# PGTNX05_mainboard.net
KiCad netlist of a schematic drawn in EAGLE
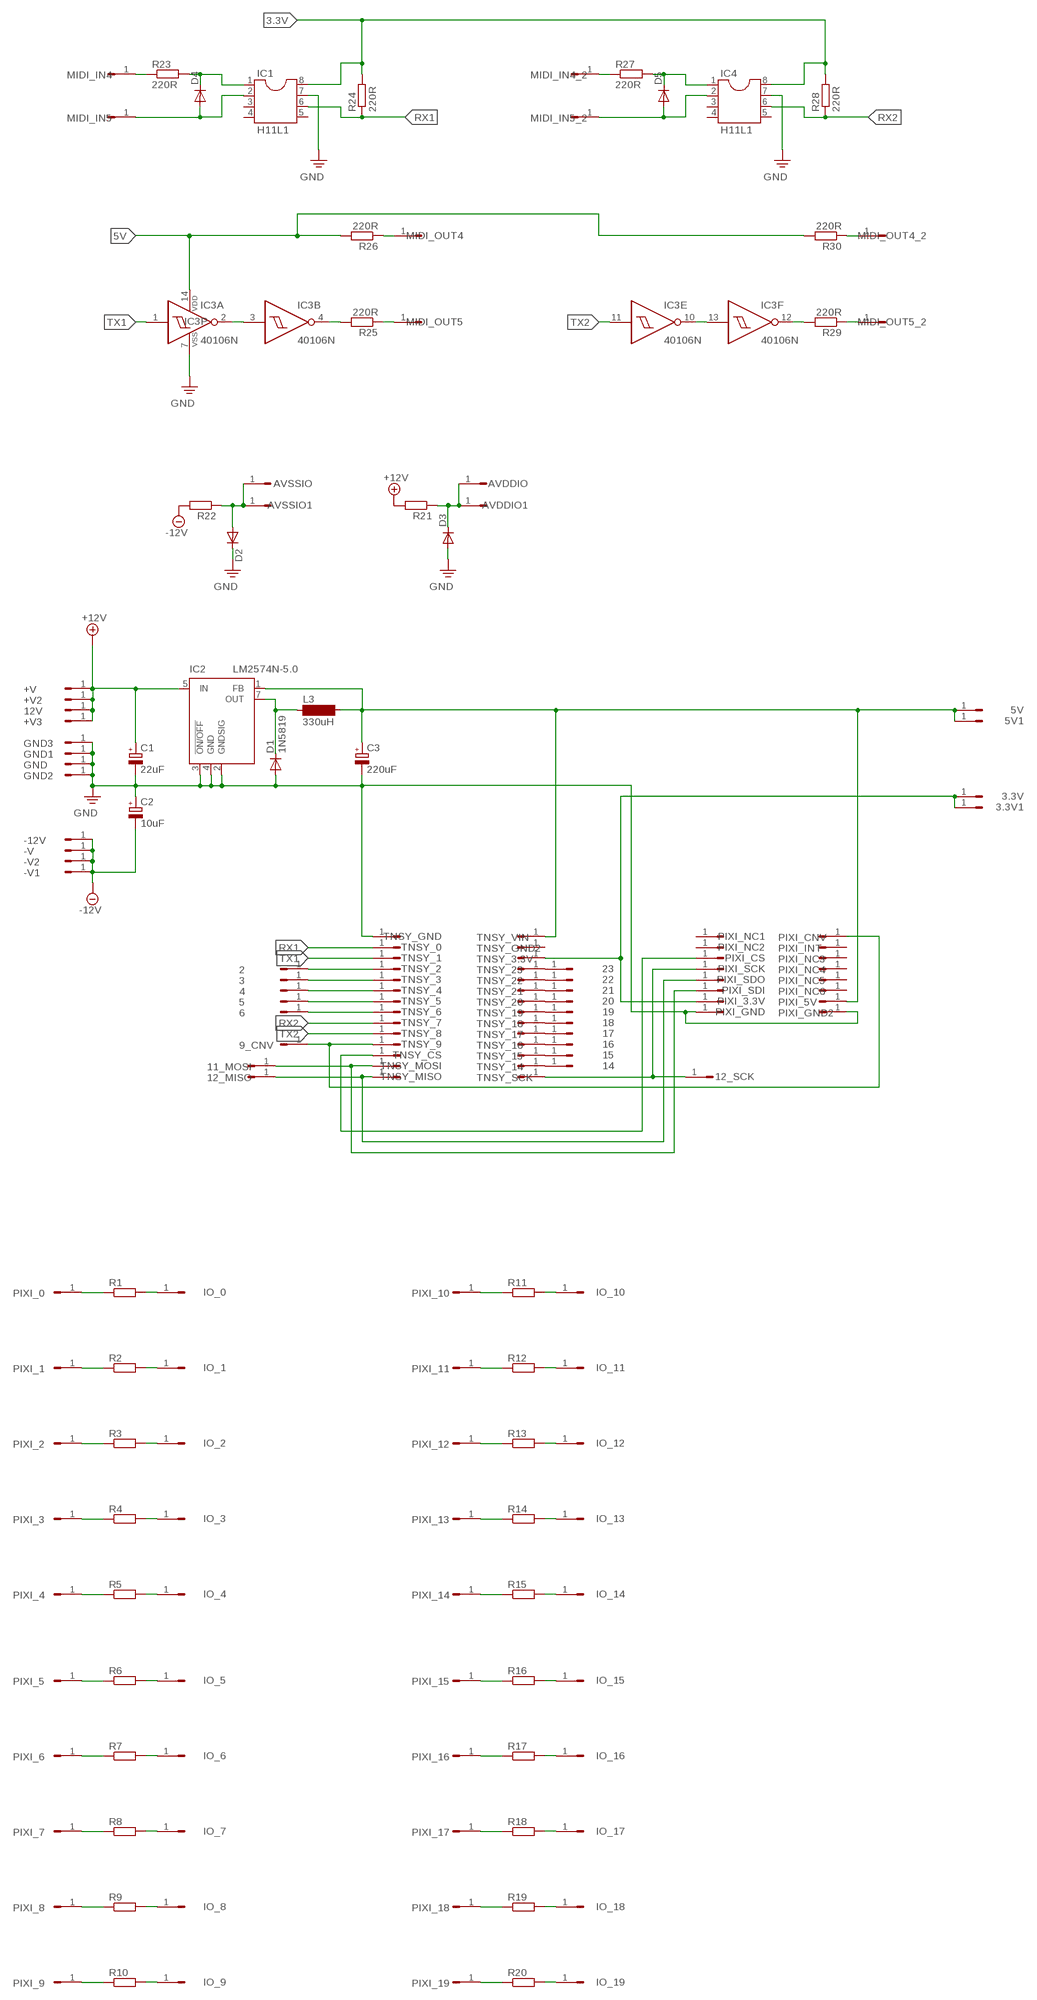
[diagram p0: schematic, sheet 1]

(export (version "E")
  (design (tool "Eeschema 10.0.6"))
  (components
    (comp (ref "+V")
      (value "HEADER/MALE/01")
      (footprint "eagle-import:HEADER_MALE_01")
      (fields (field (name "SPICEPREFIX") "X"))
      (libsource (lib "eagle-import") (part "HEADER/MALE/01"))
    )
    (comp (ref "+V2")
      (value "HEADER/MALE/01")
      (footprint "eagle-import:HEADER_MALE_01")
      (fields (field (name "SPICEPREFIX") "X"))
      (libsource (lib "eagle-import") (part "HEADER/MALE/01"))
    )
    (comp (ref "+V3")
      (value "HEADER/MALE/01")
      (footprint "eagle-import:HEADER_MALE_01")
      (fields (field (name "SPICEPREFIX") "X"))
      (libsource (lib "eagle-import") (part "HEADER/MALE/01"))
    )
    (comp (ref "-12V")
      (value "HEADER/MALE/01")
      (footprint "eagle-import:HEADER_MALE_01")
      (fields (field (name "SPICEPREFIX") "X"))
      (libsource (lib "eagle-import") (part "HEADER/MALE/01"))
    )
    (comp (ref "-V")
      (value "HEADER/MALE/01")
      (footprint "eagle-import:HEADER_MALE_01")
      (fields (field (name "SPICEPREFIX") "X"))
      (libsource (lib "eagle-import") (part "HEADER/MALE/01"))
    )
    (comp (ref "-V1")
      (value "HEADER/MALE/01")
      (footprint "eagle-import:HEADER_MALE_01")
      (fields (field (name "SPICEPREFIX") "X"))
      (libsource (lib "eagle-import") (part "HEADER/MALE/01"))
    )
    (comp (ref "-V2")
      (value "HEADER/MALE/01")
      (footprint "eagle-import:HEADER_MALE_01")
      (fields (field (name "SPICEPREFIX") "X"))
      (libsource (lib "eagle-import") (part "HEADER/MALE/01"))
    )
    (comp (ref "2")
      (value "HEADER/MALE/01")
      (footprint "eagle-import:HEADER_MALE_01")
      (fields (field (name "SPICEPREFIX") "X"))
      (libsource (lib "eagle-import") (part "HEADER/MALE/01"))
    )
    (comp (ref "3")
      (value "HEADER/MALE/01")
      (footprint "eagle-import:HEADER_MALE_01")
      (fields (field (name "SPICEPREFIX") "X"))
      (libsource (lib "eagle-import") (part "HEADER/MALE/01"))
    )
    (comp (ref "3.3V")
      (value "HEADER/MALE/01")
      (footprint "eagle-import:HEADER_MALE_01")
      (fields (field (name "SPICEPREFIX") "X"))
      (libsource (lib "eagle-import") (part "HEADER/MALE/01"))
    )
    (comp (ref "3.3V1")
      (value "HEADER/MALE/01")
      (footprint "eagle-import:HEADER_MALE_01")
      (fields (field (name "SPICEPREFIX") "X"))
      (libsource (lib "eagle-import") (part "HEADER/MALE/01"))
    )
    (comp (ref "4")
      (value "HEADER/MALE/01")
      (footprint "eagle-import:HEADER_MALE_01")
      (fields (field (name "SPICEPREFIX") "X"))
      (libsource (lib "eagle-import") (part "HEADER/MALE/01"))
    )
    (comp (ref "5")
      (value "HEADER/MALE/01")
      (footprint "eagle-import:HEADER_MALE_01")
      (fields (field (name "SPICEPREFIX") "X"))
      (libsource (lib "eagle-import") (part "HEADER/MALE/01"))
    )
    (comp (ref "5V")
      (value "HEADER/MALE/01")
      (footprint "eagle-import:HEADER_MALE_01")
      (fields (field (name "SPICEPREFIX") "X"))
      (libsource (lib "eagle-import") (part "HEADER/MALE/01"))
    )
    (comp (ref "5V1")
      (value "HEADER/MALE/01")
      (footprint "eagle-import:HEADER_MALE_01")
      (fields (field (name "SPICEPREFIX") "X"))
      (libsource (lib "eagle-import") (part "HEADER/MALE/01"))
    )
    (comp (ref "6")
      (value "HEADER/MALE/01")
      (footprint "eagle-import:HEADER_MALE_01")
      (fields (field (name "SPICEPREFIX") "X"))
      (libsource (lib "eagle-import") (part "HEADER/MALE/01"))
    )
    (comp (ref "9_CNV")
      (value "HEADER/MALE/01")
      (footprint "eagle-import:HEADER_MALE_01")
      (fields (field (name "SPICEPREFIX") "X"))
      (libsource (lib "eagle-import") (part "HEADER/MALE/01"))
    )
    (comp (ref "11_MOSI")
      (value "HEADER/MALE/01")
      (footprint "eagle-import:HEADER_MALE_01")
      (fields (field (name "SPICEPREFIX") "X"))
      (libsource (lib "eagle-import") (part "HEADER/MALE/01"))
    )
    (comp (ref "12V")
      (value "HEADER/MALE/01")
      (footprint "eagle-import:HEADER_MALE_01")
      (fields (field (name "SPICEPREFIX") "X"))
      (libsource (lib "eagle-import") (part "HEADER/MALE/01"))
    )
    (comp (ref "12_MISO")
      (value "HEADER/MALE/01")
      (footprint "eagle-import:HEADER_MALE_01")
      (fields (field (name "SPICEPREFIX") "X"))
      (libsource (lib "eagle-import") (part "HEADER/MALE/01"))
    )
    (comp (ref "12_SCK")
      (value "HEADER/MALE/01")
      (footprint "eagle-import:HEADER_MALE_01")
      (fields (field (name "SPICEPREFIX") "X"))
      (libsource (lib "eagle-import") (part "HEADER/MALE/01"))
    )
    (comp (ref "14")
      (value "HEADER/MALE/01")
      (footprint "eagle-import:HEADER_MALE_01")
      (fields (field (name "SPICEPREFIX") "X"))
      (libsource (lib "eagle-import") (part "HEADER/MALE/01"))
    )
    (comp (ref "15")
      (value "HEADER/MALE/01")
      (footprint "eagle-import:HEADER_MALE_01")
      (fields (field (name "SPICEPREFIX") "X"))
      (libsource (lib "eagle-import") (part "HEADER/MALE/01"))
    )
    (comp (ref "16")
      (value "HEADER/MALE/01")
      (footprint "eagle-import:HEADER_MALE_01")
      (fields (field (name "SPICEPREFIX") "X"))
      (libsource (lib "eagle-import") (part "HEADER/MALE/01"))
    )
    (comp (ref "17")
      (value "HEADER/MALE/01")
      (footprint "eagle-import:HEADER_MALE_01")
      (fields (field (name "SPICEPREFIX") "X"))
      (libsource (lib "eagle-import") (part "HEADER/MALE/01"))
    )
    (comp (ref "18")
      (value "HEADER/MALE/01")
      (footprint "eagle-import:HEADER_MALE_01")
      (fields (field (name "SPICEPREFIX") "X"))
      (libsource (lib "eagle-import") (part "HEADER/MALE/01"))
    )
    (comp (ref "19")
      (value "HEADER/MALE/01")
      (footprint "eagle-import:HEADER_MALE_01")
      (fields (field (name "SPICEPREFIX") "X"))
      (libsource (lib "eagle-import") (part "HEADER/MALE/01"))
    )
    (comp (ref "20")
      (value "HEADER/MALE/01")
      (footprint "eagle-import:HEADER_MALE_01")
      (fields (field (name "SPICEPREFIX") "X"))
      (libsource (lib "eagle-import") (part "HEADER/MALE/01"))
    )
    (comp (ref "21")
      (value "HEADER/MALE/01")
      (footprint "eagle-import:HEADER_MALE_01")
      (fields (field (name "SPICEPREFIX") "X"))
      (libsource (lib "eagle-import") (part "HEADER/MALE/01"))
    )
    (comp (ref "22")
      (value "HEADER/MALE/01")
      (footprint "eagle-import:HEADER_MALE_01")
      (fields (field (name "SPICEPREFIX") "X"))
      (libsource (lib "eagle-import") (part "HEADER/MALE/01"))
    )
    (comp (ref "23")
      (value "HEADER/MALE/01")
      (footprint "eagle-import:HEADER_MALE_01")
      (fields (field (name "SPICEPREFIX") "X"))
      (libsource (lib "eagle-import") (part "HEADER/MALE/01"))
    )
    (comp (ref "AVDDIO")
      (value "HEADER/MALE/01")
      (footprint "eagle-import:HEADER_MALE_01")
      (fields (field (name "SPICEPREFIX") "X"))
      (libsource (lib "eagle-import") (part "HEADER/MALE/01"))
    )
    (comp (ref "AVDDIO1")
      (value "HEADER/MALE/01")
      (footprint "eagle-import:HEADER_MALE_01")
      (fields (field (name "SPICEPREFIX") "X"))
      (libsource (lib "eagle-import") (part "HEADER/MALE/01"))
    )
    (comp (ref "AVSSIO")
      (value "HEADER/MALE/01")
      (footprint "eagle-import:HEADER_MALE_01")
      (fields (field (name "SPICEPREFIX") "X"))
      (libsource (lib "eagle-import") (part "HEADER/MALE/01"))
    )
    (comp (ref "AVSSIO1")
      (value "HEADER/MALE/01")
      (footprint "eagle-import:HEADER_MALE_01")
      (fields (field (name "SPICEPREFIX") "X"))
      (libsource (lib "eagle-import") (part "HEADER/MALE/01"))
    )
    (comp (ref "C1")
      (value "22uF")
      (footprint "eagle-import:E5-10,5")
      (fields (field (name "SPICEPREFIX") "C"))
      (libsource (lib "eagle-import") (part "CAPACITOR/POLARIZEDE5-10.5"))
    )
    (comp (ref "C2")
      (value "10uF")
      (footprint "eagle-import:E2,5-6")
      (fields (field (name "SPICEPREFIX") "C"))
      (libsource (lib "eagle-import") (part "CAPACITOR/POLARIZEDE2.5-6"))
    )
    (comp (ref "C3")
      (value "220uF")
      (footprint "eagle-import:E2,5-6")
      (fields (field (name "SPICEPREFIX") "C"))
      (libsource (lib "eagle-import") (part "CAPACITOR/POLARIZEDE2.5-6"))
    )
    (comp (ref "D1")
      (value "1N5819")
      (footprint "eagle-import:DO35-7")
      (libsource (lib "eagle-import") (part "1N4148DO35-7"))
    )
    (comp (ref "D2")
      (value "1N4148DO35-7")
      (footprint "eagle-import:DO35-7")
      (libsource (lib "eagle-import") (part "1N4148DO35-7"))
    )
    (comp (ref "D3")
      (value "1N4148DO35-7")
      (footprint "eagle-import:DO35-7")
      (libsource (lib "eagle-import") (part "1N4148DO35-7"))
    )
    (comp (ref "D4")
      (value "1N4148DO35-7")
      (footprint "eagle-import:DO35-7")
      (libsource (lib "eagle-import") (part "1N4148DO35-7"))
    )
    (comp (ref "D5")
      (value "1N4148DO35-7")
      (footprint "eagle-import:DO35-7")
      (libsource (lib "eagle-import") (part "1N4148DO35-7"))
    )
    (comp (ref "GND")
      (value "HEADER/MALE/01")
      (footprint "eagle-import:HEADER_MALE_01")
      (fields (field (name "SPICEPREFIX") "X"))
      (libsource (lib "eagle-import") (part "HEADER/MALE/01"))
    )
    (comp (ref "GND1")
      (value "HEADER/MALE/01")
      (footprint "eagle-import:HEADER_MALE_01")
      (fields (field (name "SPICEPREFIX") "X"))
      (libsource (lib "eagle-import") (part "HEADER/MALE/01"))
    )
    (comp (ref "GND2")
      (value "HEADER/MALE/01")
      (footprint "eagle-import:HEADER_MALE_01")
      (fields (field (name "SPICEPREFIX") "X"))
      (libsource (lib "eagle-import") (part "HEADER/MALE/01"))
    )
    (comp (ref "GND3")
      (value "HEADER/MALE/01")
      (footprint "eagle-import:HEADER_MALE_01")
      (fields (field (name "SPICEPREFIX") "X"))
      (libsource (lib "eagle-import") (part "HEADER/MALE/01"))
    )
    (comp (ref "IC1")
      (value "H11L1")
      (footprint "eagle-import:DIL08")
      (libsource (lib "eagle-import") (part "DIL8"))
    )
    (comp (ref "IC2")
      (value "LM2574N-5.0")
      (footprint "eagle-import:DIL08")
      (libsource (lib "eagle-import") (part "LM2574?-N5.0"))
    )
    (comp (ref "IC3")
      (value "40106N")
      (footprint "eagle-import:DIL14")
      (libsource (lib "eagle-import") (part "40106N"))
    )
    (comp (ref "IC4")
      (value "H11L1")
      (footprint "eagle-import:DIL08")
      (libsource (lib "eagle-import") (part "DIL8"))
    )
    (comp (ref "IO_0")
      (value "HEADER/MALE/01")
      (footprint "eagle-import:HEADER_MALE_01")
      (fields (field (name "SPICEPREFIX") "X"))
      (libsource (lib "eagle-import") (part "HEADER/MALE/01"))
    )
    (comp (ref "IO_1")
      (value "HEADER/MALE/01")
      (footprint "eagle-import:HEADER_MALE_01")
      (fields (field (name "SPICEPREFIX") "X"))
      (libsource (lib "eagle-import") (part "HEADER/MALE/01"))
    )
    (comp (ref "IO_2")
      (value "HEADER/MALE/01")
      (footprint "eagle-import:HEADER_MALE_01")
      (fields (field (name "SPICEPREFIX") "X"))
      (libsource (lib "eagle-import") (part "HEADER/MALE/01"))
    )
    (comp (ref "IO_3")
      (value "HEADER/MALE/01")
      (footprint "eagle-import:HEADER_MALE_01")
      (fields (field (name "SPICEPREFIX") "X"))
      (libsource (lib "eagle-import") (part "HEADER/MALE/01"))
    )
    (comp (ref "IO_4")
      (value "HEADER/MALE/01")
      (footprint "eagle-import:HEADER_MALE_01")
      (fields (field (name "SPICEPREFIX") "X"))
      (libsource (lib "eagle-import") (part "HEADER/MALE/01"))
    )
    (comp (ref "IO_5")
      (value "HEADER/MALE/01")
      (footprint "eagle-import:HEADER_MALE_01")
      (fields (field (name "SPICEPREFIX") "X"))
      (libsource (lib "eagle-import") (part "HEADER/MALE/01"))
    )
    (comp (ref "IO_6")
      (value "HEADER/MALE/01")
      (footprint "eagle-import:HEADER_MALE_01")
      (fields (field (name "SPICEPREFIX") "X"))
      (libsource (lib "eagle-import") (part "HEADER/MALE/01"))
    )
    (comp (ref "IO_7")
      (value "HEADER/MALE/01")
      (footprint "eagle-import:HEADER_MALE_01")
      (fields (field (name "SPICEPREFIX") "X"))
      (libsource (lib "eagle-import") (part "HEADER/MALE/01"))
    )
    (comp (ref "IO_8")
      (value "HEADER/MALE/01")
      (footprint "eagle-import:HEADER_MALE_01")
      (fields (field (name "SPICEPREFIX") "X"))
      (libsource (lib "eagle-import") (part "HEADER/MALE/01"))
    )
    (comp (ref "IO_9")
      (value "HEADER/MALE/01")
      (footprint "eagle-import:HEADER_MALE_01")
      (fields (field (name "SPICEPREFIX") "X"))
      (libsource (lib "eagle-import") (part "HEADER/MALE/01"))
    )
    (comp (ref "IO_10")
      (value "HEADER/MALE/01")
      (footprint "eagle-import:HEADER_MALE_01")
      (fields (field (name "SPICEPREFIX") "X"))
      (libsource (lib "eagle-import") (part "HEADER/MALE/01"))
    )
    (comp (ref "IO_11")
      (value "HEADER/MALE/01")
      (footprint "eagle-import:HEADER_MALE_01")
      (fields (field (name "SPICEPREFIX") "X"))
      (libsource (lib "eagle-import") (part "HEADER/MALE/01"))
    )
    (comp (ref "IO_12")
      (value "HEADER/MALE/01")
      (footprint "eagle-import:HEADER_MALE_01")
      (fields (field (name "SPICEPREFIX") "X"))
      (libsource (lib "eagle-import") (part "HEADER/MALE/01"))
    )
    (comp (ref "IO_13")
      (value "HEADER/MALE/01")
      (footprint "eagle-import:HEADER_MALE_01")
      (fields (field (name "SPICEPREFIX") "X"))
      (libsource (lib "eagle-import") (part "HEADER/MALE/01"))
    )
    (comp (ref "IO_14")
      (value "HEADER/MALE/01")
      (footprint "eagle-import:HEADER_MALE_01")
      (fields (field (name "SPICEPREFIX") "X"))
      (libsource (lib "eagle-import") (part "HEADER/MALE/01"))
    )
    (comp (ref "IO_15")
      (value "HEADER/MALE/01")
      (footprint "eagle-import:HEADER_MALE_01")
      (fields (field (name "SPICEPREFIX") "X"))
      (libsource (lib "eagle-import") (part "HEADER/MALE/01"))
    )
    (comp (ref "IO_16")
      (value "HEADER/MALE/01")
      (footprint "eagle-import:HEADER_MALE_01")
      (fields (field (name "SPICEPREFIX") "X"))
      (libsource (lib "eagle-import") (part "HEADER/MALE/01"))
    )
    (comp (ref "IO_17")
      (value "HEADER/MALE/01")
      (footprint "eagle-import:HEADER_MALE_01")
      (fields (field (name "SPICEPREFIX") "X"))
      (libsource (lib "eagle-import") (part "HEADER/MALE/01"))
    )
    (comp (ref "IO_18")
      (value "HEADER/MALE/01")
      (footprint "eagle-import:HEADER_MALE_01")
      (fields (field (name "SPICEPREFIX") "X"))
      (libsource (lib "eagle-import") (part "HEADER/MALE/01"))
    )
    (comp (ref "IO_19")
      (value "HEADER/MALE/01")
      (footprint "eagle-import:HEADER_MALE_01")
      (fields (field (name "SPICEPREFIX") "X"))
      (libsource (lib "eagle-import") (part "HEADER/MALE/01"))
    )
    (comp (ref "L3")
      (value "330uH")
      (footprint "eagle-import:BS11")
      (libsource (lib "eagle-import") (part "BS11"))
    )
    (comp (ref "MIDI_IN4")
      (value "HEADER/MALE/01")
      (footprint "eagle-import:HEADER_MALE_01")
      (fields (field (name "SPICEPREFIX") "X"))
      (libsource (lib "eagle-import") (part "HEADER/MALE/01"))
    )
    (comp (ref "MIDI_IN4_2")
      (value "HEADER/MALE/01")
      (footprint "eagle-import:HEADER_MALE_01")
      (fields (field (name "SPICEPREFIX") "X"))
      (libsource (lib "eagle-import") (part "HEADER/MALE/01"))
    )
    (comp (ref "MIDI_IN5")
      (value "HEADER/MALE/01")
      (footprint "eagle-import:HEADER_MALE_01")
      (fields (field (name "SPICEPREFIX") "X"))
      (libsource (lib "eagle-import") (part "HEADER/MALE/01"))
    )
    (comp (ref "MIDI_IN5_2")
      (value "HEADER/MALE/01")
      (footprint "eagle-import:HEADER_MALE_01")
      (fields (field (name "SPICEPREFIX") "X"))
      (libsource (lib "eagle-import") (part "HEADER/MALE/01"))
    )
    (comp (ref "MIDI_OUT4")
      (value "HEADER/MALE/01")
      (footprint "eagle-import:HEADER_MALE_01")
      (fields (field (name "SPICEPREFIX") "X"))
      (libsource (lib "eagle-import") (part "HEADER/MALE/01"))
    )
    (comp (ref "MIDI_OUT4_2")
      (value "HEADER/MALE/01")
      (footprint "eagle-import:HEADER_MALE_01")
      (fields (field (name "SPICEPREFIX") "X"))
      (libsource (lib "eagle-import") (part "HEADER/MALE/01"))
    )
    (comp (ref "MIDI_OUT5")
      (value "HEADER/MALE/01")
      (footprint "eagle-import:HEADER_MALE_01")
      (fields (field (name "SPICEPREFIX") "X"))
      (libsource (lib "eagle-import") (part "HEADER/MALE/01"))
    )
    (comp (ref "MIDI_OUT5_2")
      (value "HEADER/MALE/01")
      (footprint "eagle-import:HEADER_MALE_01")
      (fields (field (name "SPICEPREFIX") "X"))
      (libsource (lib "eagle-import") (part "HEADER/MALE/01"))
    )
    (comp (ref "PIXI_0")
      (value "HEADER/MALE/01")
      (footprint "eagle-import:HEADER_MALE_01")
      (fields (field (name "SPICEPREFIX") "X"))
      (libsource (lib "eagle-import") (part "HEADER/MALE/01"))
    )
    (comp (ref "PIXI_1")
      (value "HEADER/MALE/01")
      (footprint "eagle-import:HEADER_MALE_01")
      (fields (field (name "SPICEPREFIX") "X"))
      (libsource (lib "eagle-import") (part "HEADER/MALE/01"))
    )
    (comp (ref "PIXI_2")
      (value "HEADER/MALE/01")
      (footprint "eagle-import:HEADER_MALE_01")
      (fields (field (name "SPICEPREFIX") "X"))
      (libsource (lib "eagle-import") (part "HEADER/MALE/01"))
    )
    (comp (ref "PIXI_3")
      (value "HEADER/MALE/01")
      (footprint "eagle-import:HEADER_MALE_01")
      (fields (field (name "SPICEPREFIX") "X"))
      (libsource (lib "eagle-import") (part "HEADER/MALE/01"))
    )
    (comp (ref "PIXI_3.3V")
      (value "HEADER/MALE/01")
      (footprint "eagle-import:HEADER_MALE_01")
      (fields (field (name "SPICEPREFIX") "X"))
      (libsource (lib "eagle-import") (part "HEADER/MALE/01"))
    )
    (comp (ref "PIXI_4")
      (value "HEADER/MALE/01")
      (footprint "eagle-import:HEADER_MALE_01")
      (fields (field (name "SPICEPREFIX") "X"))
      (libsource (lib "eagle-import") (part "HEADER/MALE/01"))
    )
    (comp (ref "PIXI_5")
      (value "HEADER/MALE/01")
      (footprint "eagle-import:HEADER_MALE_01")
      (fields (field (name "SPICEPREFIX") "X"))
      (libsource (lib "eagle-import") (part "HEADER/MALE/01"))
    )
    (comp (ref "PIXI_5V")
      (value "HEADER/MALE/01")
      (footprint "eagle-import:HEADER_MALE_01")
      (fields (field (name "SPICEPREFIX") "X"))
      (libsource (lib "eagle-import") (part "HEADER/MALE/01"))
    )
    (comp (ref "PIXI_6")
      (value "HEADER/MALE/01")
      (footprint "eagle-import:HEADER_MALE_01")
      (fields (field (name "SPICEPREFIX") "X"))
      (libsource (lib "eagle-import") (part "HEADER/MALE/01"))
    )
    (comp (ref "PIXI_7")
      (value "HEADER/MALE/01")
      (footprint "eagle-import:HEADER_MALE_01")
      (fields (field (name "SPICEPREFIX") "X"))
      (libsource (lib "eagle-import") (part "HEADER/MALE/01"))
    )
    (comp (ref "PIXI_8")
      (value "HEADER/MALE/01")
      (footprint "eagle-import:HEADER_MALE_01")
      (fields (field (name "SPICEPREFIX") "X"))
      (libsource (lib "eagle-import") (part "HEADER/MALE/01"))
    )
    (comp (ref "PIXI_9")
      (value "HEADER/MALE/01")
      (footprint "eagle-import:HEADER_MALE_01")
      (fields (field (name "SPICEPREFIX") "X"))
      (libsource (lib "eagle-import") (part "HEADER/MALE/01"))
    )
    (comp (ref "PIXI_10")
      (value "HEADER/MALE/01")
      (footprint "eagle-import:HEADER_MALE_01")
      (fields (field (name "SPICEPREFIX") "X"))
      (libsource (lib "eagle-import") (part "HEADER/MALE/01"))
    )
    (comp (ref "PIXI_11")
      (value "HEADER/MALE/01")
      (footprint "eagle-import:HEADER_MALE_01")
      (fields (field (name "SPICEPREFIX") "X"))
      (libsource (lib "eagle-import") (part "HEADER/MALE/01"))
    )
    (comp (ref "PIXI_12")
      (value "HEADER/MALE/01")
      (footprint "eagle-import:HEADER_MALE_01")
      (fields (field (name "SPICEPREFIX") "X"))
      (libsource (lib "eagle-import") (part "HEADER/MALE/01"))
    )
    (comp (ref "PIXI_13")
      (value "HEADER/MALE/01")
      (footprint "eagle-import:HEADER_MALE_01")
      (fields (field (name "SPICEPREFIX") "X"))
      (libsource (lib "eagle-import") (part "HEADER/MALE/01"))
    )
    (comp (ref "PIXI_14")
      (value "HEADER/MALE/01")
      (footprint "eagle-import:HEADER_MALE_01")
      (fields (field (name "SPICEPREFIX") "X"))
      (libsource (lib "eagle-import") (part "HEADER/MALE/01"))
    )
    (comp (ref "PIXI_15")
      (value "HEADER/MALE/01")
      (footprint "eagle-import:HEADER_MALE_01")
      (fields (field (name "SPICEPREFIX") "X"))
      (libsource (lib "eagle-import") (part "HEADER/MALE/01"))
    )
    (comp (ref "PIXI_16")
      (value "HEADER/MALE/01")
      (footprint "eagle-import:HEADER_MALE_01")
      (fields (field (name "SPICEPREFIX") "X"))
      (libsource (lib "eagle-import") (part "HEADER/MALE/01"))
    )
    (comp (ref "PIXI_17")
      (value "HEADER/MALE/01")
      (footprint "eagle-import:HEADER_MALE_01")
      (fields (field (name "SPICEPREFIX") "X"))
      (libsource (lib "eagle-import") (part "HEADER/MALE/01"))
    )
    (comp (ref "PIXI_18")
      (value "HEADER/MALE/01")
      (footprint "eagle-import:HEADER_MALE_01")
      (fields (field (name "SPICEPREFIX") "X"))
      (libsource (lib "eagle-import") (part "HEADER/MALE/01"))
    )
    (comp (ref "PIXI_19")
      (value "HEADER/MALE/01")
      (footprint "eagle-import:HEADER_MALE_01")
      (fields (field (name "SPICEPREFIX") "X"))
      (libsource (lib "eagle-import") (part "HEADER/MALE/01"))
    )
    (comp (ref "PIXI_CNV")
      (value "HEADER/MALE/01")
      (footprint "eagle-import:HEADER_MALE_01")
      (fields (field (name "SPICEPREFIX") "X"))
      (libsource (lib "eagle-import") (part "HEADER/MALE/01"))
    )
    (comp (ref "PIXI_CS")
      (value "HEADER/MALE/01")
      (footprint "eagle-import:HEADER_MALE_01")
      (fields (field (name "SPICEPREFIX") "X"))
      (libsource (lib "eagle-import") (part "HEADER/MALE/01"))
    )
    (comp (ref "PIXI_GND")
      (value "HEADER/MALE/01")
      (footprint "eagle-import:HEADER_MALE_01")
      (fields (field (name "SPICEPREFIX") "X"))
      (libsource (lib "eagle-import") (part "HEADER/MALE/01"))
    )
    (comp (ref "PIXI_GND2")
      (value "HEADER/MALE/01")
      (footprint "eagle-import:HEADER_MALE_01")
      (fields (field (name "SPICEPREFIX") "X"))
      (libsource (lib "eagle-import") (part "HEADER/MALE/01"))
    )
    (comp (ref "PIXI_INT")
      (value "HEADER/MALE/01")
      (footprint "eagle-import:HEADER_MALE_01")
      (fields (field (name "SPICEPREFIX") "X"))
      (libsource (lib "eagle-import") (part "HEADER/MALE/01"))
    )
    (comp (ref "PIXI_NC1")
      (value "HEADER/MALE/01")
      (footprint "eagle-import:HEADER_MALE_01")
      (fields (field (name "SPICEPREFIX") "X"))
      (libsource (lib "eagle-import") (part "HEADER/MALE/01"))
    )
    (comp (ref "PIXI_NC2")
      (value "HEADER/MALE/01")
      (footprint "eagle-import:HEADER_MALE_01")
      (fields (field (name "SPICEPREFIX") "X"))
      (libsource (lib "eagle-import") (part "HEADER/MALE/01"))
    )
    (comp (ref "PIXI_NC3")
      (value "HEADER/MALE/01")
      (footprint "eagle-import:HEADER_MALE_01")
      (fields (field (name "SPICEPREFIX") "X"))
      (libsource (lib "eagle-import") (part "HEADER/MALE/01"))
    )
    (comp (ref "PIXI_NC4")
      (value "HEADER/MALE/01")
      (footprint "eagle-import:HEADER_MALE_01")
      (fields (field (name "SPICEPREFIX") "X"))
      (libsource (lib "eagle-import") (part "HEADER/MALE/01"))
    )
    (comp (ref "PIXI_NC5")
      (value "HEADER/MALE/01")
      (footprint "eagle-import:HEADER_MALE_01")
      (fields (field (name "SPICEPREFIX") "X"))
      (libsource (lib "eagle-import") (part "HEADER/MALE/01"))
    )
    (comp (ref "PIXI_NC6")
      (value "HEADER/MALE/01")
      (footprint "eagle-import:HEADER_MALE_01")
      (fields (field (name "SPICEPREFIX") "X"))
      (libsource (lib "eagle-import") (part "HEADER/MALE/01"))
    )
    (comp (ref "PIXI_SCK")
      (value "HEADER/MALE/01")
      (footprint "eagle-import:HEADER_MALE_01")
      (fields (field (name "SPICEPREFIX") "X"))
      (libsource (lib "eagle-import") (part "HEADER/MALE/01"))
    )
    (comp (ref "PIXI_SDI")
      (value "HEADER/MALE/01")
      (footprint "eagle-import:HEADER_MALE_01")
      (fields (field (name "SPICEPREFIX") "X"))
      (libsource (lib "eagle-import") (part "HEADER/MALE/01"))
    )
    (comp (ref "PIXI_SDO")
      (value "HEADER/MALE/01")
      (footprint "eagle-import:HEADER_MALE_01")
      (fields (field (name "SPICEPREFIX") "X"))
      (libsource (lib "eagle-import") (part "HEADER/MALE/01"))
    )
    (comp (ref "R1")
      (value "RESISTORRESISTOR/UPRIGHT/7.5")
      (footprint "eagle-import:RESISTOR_7.5")
      (libsource (lib "eagle-import") (part "RESISTORRESISTOR/UPRIGHT/7.5"))
    )
    (comp (ref "R2")
      (value "RESISTORRESISTOR/UPRIGHT/7.5")
      (footprint "eagle-import:RESISTOR_7.5")
      (libsource (lib "eagle-import") (part "RESISTORRESISTOR/UPRIGHT/7.5"))
    )
    (comp (ref "R3")
      (value "RESISTORRESISTOR/UPRIGHT/7.5")
      (footprint "eagle-import:RESISTOR_7.5")
      (libsource (lib "eagle-import") (part "RESISTORRESISTOR/UPRIGHT/7.5"))
    )
    (comp (ref "R4")
      (value "RESISTORRESISTOR/UPRIGHT/7.5")
      (footprint "eagle-import:RESISTOR_7.5")
      (libsource (lib "eagle-import") (part "RESISTORRESISTOR/UPRIGHT/7.5"))
    )
    (comp (ref "R5")
      (value "RESISTORRESISTOR/UPRIGHT/7.5")
      (footprint "eagle-import:RESISTOR_7.5")
      (libsource (lib "eagle-import") (part "RESISTORRESISTOR/UPRIGHT/7.5"))
    )
    (comp (ref "R6")
      (value "RESISTORRESISTOR/UPRIGHT/7.5")
      (footprint "eagle-import:RESISTOR_7.5")
      (libsource (lib "eagle-import") (part "RESISTORRESISTOR/UPRIGHT/7.5"))
    )
    (comp (ref "R7")
      (value "RESISTORRESISTOR/UPRIGHT/7.5")
      (footprint "eagle-import:RESISTOR_7.5")
      (libsource (lib "eagle-import") (part "RESISTORRESISTOR/UPRIGHT/7.5"))
    )
    (comp (ref "R8")
      (value "RESISTORRESISTOR/UPRIGHT/7.5")
      (footprint "eagle-import:RESISTOR_7.5")
      (libsource (lib "eagle-import") (part "RESISTORRESISTOR/UPRIGHT/7.5"))
    )
    (comp (ref "R9")
      (value "RESISTORRESISTOR/UPRIGHT/7.5")
      (footprint "eagle-import:RESISTOR_7.5")
      (libsource (lib "eagle-import") (part "RESISTORRESISTOR/UPRIGHT/7.5"))
    )
    (comp (ref "R10")
      (value "RESISTORRESISTOR/UPRIGHT/7.5")
      (footprint "eagle-import:RESISTOR_7.5")
      (libsource (lib "eagle-import") (part "RESISTORRESISTOR/UPRIGHT/7.5"))
    )
    (comp (ref "R11")
      (value "RESISTORRESISTOR/UPRIGHT/7.5")
      (footprint "eagle-import:RESISTOR_7.5")
      (libsource (lib "eagle-import") (part "RESISTORRESISTOR/UPRIGHT/7.5"))
    )
    (comp (ref "R12")
      (value "RESISTORRESISTOR/UPRIGHT/7.5")
      (footprint "eagle-import:RESISTOR_7.5")
      (libsource (lib "eagle-import") (part "RESISTORRESISTOR/UPRIGHT/7.5"))
    )
    (comp (ref "R13")
      (value "RESISTORRESISTOR/UPRIGHT/7.5")
      (footprint "eagle-import:RESISTOR_7.5")
      (libsource (lib "eagle-import") (part "RESISTORRESISTOR/UPRIGHT/7.5"))
    )
    (comp (ref "R14")
      (value "RESISTORRESISTOR/UPRIGHT/7.5")
      (footprint "eagle-import:RESISTOR_7.5")
      (libsource (lib "eagle-import") (part "RESISTORRESISTOR/UPRIGHT/7.5"))
    )
    (comp (ref "R15")
      (value "RESISTORRESISTOR/UPRIGHT/7.5")
      (footprint "eagle-import:RESISTOR_7.5")
      (libsource (lib "eagle-import") (part "RESISTORRESISTOR/UPRIGHT/7.5"))
    )
    (comp (ref "R16")
      (value "RESISTORRESISTOR/UPRIGHT/7.5")
      (footprint "eagle-import:RESISTOR_7.5")
      (libsource (lib "eagle-import") (part "RESISTORRESISTOR/UPRIGHT/7.5"))
    )
    (comp (ref "R17")
      (value "RESISTORRESISTOR/UPRIGHT/7.5")
      (footprint "eagle-import:RESISTOR_7.5")
      (libsource (lib "eagle-import") (part "RESISTORRESISTOR/UPRIGHT/7.5"))
    )
    (comp (ref "R18")
      (value "RESISTORRESISTOR/UPRIGHT/7.5")
      (footprint "eagle-import:RESISTOR_7.5")
      (libsource (lib "eagle-import") (part "RESISTORRESISTOR/UPRIGHT/7.5"))
    )
    (comp (ref "R19")
      (value "RESISTORRESISTOR/UPRIGHT/7.5")
      (footprint "eagle-import:RESISTOR_7.5")
      (libsource (lib "eagle-import") (part "RESISTORRESISTOR/UPRIGHT/7.5"))
    )
    (comp (ref "R20")
      (value "RESISTORRESISTOR/UPRIGHT/7.5")
      (footprint "eagle-import:RESISTOR_7.5")
      (libsource (lib "eagle-import") (part "RESISTORRESISTOR/UPRIGHT/7.5"))
    )
    (comp (ref "R21")
      (value "RESISTORRESISTOR/UPRIGHT/7.5")
      (footprint "eagle-import:RESISTOR_7.5")
      (libsource (lib "eagle-import") (part "RESISTORRESISTOR/UPRIGHT/7.5"))
    )
    (comp (ref "R22")
      (value "RESISTORRESISTOR/UPRIGHT/7.5")
      (footprint "eagle-import:RESISTOR_7.5")
      (libsource (lib "eagle-import") (part "RESISTORRESISTOR/UPRIGHT/7.5"))
    )
    (comp (ref "R23")
      (value "220R")
      (footprint "eagle-import:RESISTOR_7.5")
      (libsource (lib "eagle-import") (part "RESISTORRESISTOR/UPRIGHT/7.5"))
    )
    (comp (ref "R24")
      (value "220R")
      (footprint "eagle-import:RESISTOR_7.5")
      (libsource (lib "eagle-import") (part "RESISTORRESISTOR/UPRIGHT/7.5"))
    )
    (comp (ref "R25")
      (value "220R")
      (footprint "eagle-import:RESISTOR_7.5")
      (libsource (lib "eagle-import") (part "RESISTORRESISTOR/UPRIGHT/7.5"))
    )
    (comp (ref "R26")
      (value "220R")
      (footprint "eagle-import:RESISTOR_7.5")
      (libsource (lib "eagle-import") (part "RESISTORRESISTOR/UPRIGHT/7.5"))
    )
    (comp (ref "R27")
      (value "220R")
      (footprint "eagle-import:RESISTOR_7.5")
      (libsource (lib "eagle-import") (part "RESISTORRESISTOR/UPRIGHT/7.5"))
    )
    (comp (ref "R28")
      (value "220R")
      (footprint "eagle-import:RESISTOR_7.5")
      (libsource (lib "eagle-import") (part "RESISTORRESISTOR/UPRIGHT/7.5"))
    )
    (comp (ref "R29")
      (value "220R")
      (footprint "eagle-import:RESISTOR_7.5")
      (libsource (lib "eagle-import") (part "RESISTORRESISTOR/UPRIGHT/7.5"))
    )
    (comp (ref "R30")
      (value "220R")
      (footprint "eagle-import:RESISTOR_7.5")
      (libsource (lib "eagle-import") (part "RESISTORRESISTOR/UPRIGHT/7.5"))
    )
    (comp (ref "TNSY_0")
      (value "HEADER/MALE/01")
      (footprint "eagle-import:HEADER_MALE_01")
      (fields (field (name "SPICEPREFIX") "X"))
      (libsource (lib "eagle-import") (part "HEADER/MALE/01"))
    )
    (comp (ref "TNSY_1")
      (value "HEADER/MALE/01")
      (footprint "eagle-import:HEADER_MALE_01")
      (fields (field (name "SPICEPREFIX") "X"))
      (libsource (lib "eagle-import") (part "HEADER/MALE/01"))
    )
    (comp (ref "TNSY_2")
      (value "HEADER/MALE/01")
      (footprint "eagle-import:HEADER_MALE_01")
      (fields (field (name "SPICEPREFIX") "X"))
      (libsource (lib "eagle-import") (part "HEADER/MALE/01"))
    )
    (comp (ref "TNSY_3")
      (value "HEADER/MALE/01")
      (footprint "eagle-import:HEADER_MALE_01")
      (fields (field (name "SPICEPREFIX") "X"))
      (libsource (lib "eagle-import") (part "HEADER/MALE/01"))
    )
    (comp (ref "TNSY_3.3V")
      (value "HEADER/MALE/01")
      (footprint "eagle-import:HEADER_MALE_01")
      (fields (field (name "SPICEPREFIX") "X"))
      (libsource (lib "eagle-import") (part "HEADER/MALE/01"))
    )
    (comp (ref "TNSY_4")
      (value "HEADER/MALE/01")
      (footprint "eagle-import:HEADER_MALE_01")
      (fields (field (name "SPICEPREFIX") "X"))
      (libsource (lib "eagle-import") (part "HEADER/MALE/01"))
    )
    (comp (ref "TNSY_5")
      (value "HEADER/MALE/01")
      (footprint "eagle-import:HEADER_MALE_01")
      (fields (field (name "SPICEPREFIX") "X"))
      (libsource (lib "eagle-import") (part "HEADER/MALE/01"))
    )
    (comp (ref "TNSY_6")
      (value "HEADER/MALE/01")
      (footprint "eagle-import:HEADER_MALE_01")
      (fields (field (name "SPICEPREFIX") "X"))
      (libsource (lib "eagle-import") (part "HEADER/MALE/01"))
    )
    (comp (ref "TNSY_7")
      (value "HEADER/MALE/01")
      (footprint "eagle-import:HEADER_MALE_01")
      (fields (field (name "SPICEPREFIX") "X"))
      (libsource (lib "eagle-import") (part "HEADER/MALE/01"))
    )
    (comp (ref "TNSY_8")
      (value "HEADER/MALE/01")
      (footprint "eagle-import:HEADER_MALE_01")
      (fields (field (name "SPICEPREFIX") "X"))
      (libsource (lib "eagle-import") (part "HEADER/MALE/01"))
    )
    (comp (ref "TNSY_9")
      (value "HEADER/MALE/01")
      (footprint "eagle-import:HEADER_MALE_01")
      (fields (field (name "SPICEPREFIX") "X"))
      (libsource (lib "eagle-import") (part "HEADER/MALE/01"))
    )
    (comp (ref "TNSY_14")
      (value "HEADER/MALE/01")
      (footprint "eagle-import:HEADER_MALE_01")
      (fields (field (name "SPICEPREFIX") "X"))
      (libsource (lib "eagle-import") (part "HEADER/MALE/01"))
    )
    (comp (ref "TNSY_15")
      (value "HEADER/MALE/01")
      (footprint "eagle-import:HEADER_MALE_01")
      (fields (field (name "SPICEPREFIX") "X"))
      (libsource (lib "eagle-import") (part "HEADER/MALE/01"))
    )
    (comp (ref "TNSY_16")
      (value "HEADER/MALE/01")
      (footprint "eagle-import:HEADER_MALE_01")
      (fields (field (name "SPICEPREFIX") "X"))
      (libsource (lib "eagle-import") (part "HEADER/MALE/01"))
    )
    (comp (ref "TNSY_17")
      (value "HEADER/MALE/01")
      (footprint "eagle-import:HEADER_MALE_01")
      (fields (field (name "SPICEPREFIX") "X"))
      (libsource (lib "eagle-import") (part "HEADER/MALE/01"))
    )
    (comp (ref "TNSY_18")
      (value "HEADER/MALE/01")
      (footprint "eagle-import:HEADER_MALE_01")
      (fields (field (name "SPICEPREFIX") "X"))
      (libsource (lib "eagle-import") (part "HEADER/MALE/01"))
    )
    (comp (ref "TNSY_19")
      (value "HEADER/MALE/01")
      (footprint "eagle-import:HEADER_MALE_01")
      (fields (field (name "SPICEPREFIX") "X"))
      (libsource (lib "eagle-import") (part "HEADER/MALE/01"))
    )
    (comp (ref "TNSY_20")
      (value "HEADER/MALE/01")
      (footprint "eagle-import:HEADER_MALE_01")
      (fields (field (name "SPICEPREFIX") "X"))
      (libsource (lib "eagle-import") (part "HEADER/MALE/01"))
    )
    (comp (ref "TNSY_21")
      (value "HEADER/MALE/01")
      (footprint "eagle-import:HEADER_MALE_01")
      (fields (field (name "SPICEPREFIX") "X"))
      (libsource (lib "eagle-import") (part "HEADER/MALE/01"))
    )
    (comp (ref "TNSY_22")
      (value "HEADER/MALE/01")
      (footprint "eagle-import:HEADER_MALE_01")
      (fields (field (name "SPICEPREFIX") "X"))
      (libsource (lib "eagle-import") (part "HEADER/MALE/01"))
    )
    (comp (ref "TNSY_23")
      (value "HEADER/MALE/01")
      (footprint "eagle-import:HEADER_MALE_01")
      (fields (field (name "SPICEPREFIX") "X"))
      (libsource (lib "eagle-import") (part "HEADER/MALE/01"))
    )
    (comp (ref "TNSY_CS")
      (value "HEADER/MALE/01")
      (footprint "eagle-import:HEADER_MALE_01")
      (fields (field (name "SPICEPREFIX") "X"))
      (libsource (lib "eagle-import") (part "HEADER/MALE/01"))
    )
    (comp (ref "TNSY_GND")
      (value "HEADER/MALE/01")
      (footprint "eagle-import:HEADER_MALE_01")
      (fields (field (name "SPICEPREFIX") "X"))
      (libsource (lib "eagle-import") (part "HEADER/MALE/01"))
    )
    (comp (ref "TNSY_GND2")
      (value "HEADER/MALE/01")
      (footprint "eagle-import:HEADER_MALE_01")
      (fields (field (name "SPICEPREFIX") "X"))
      (libsource (lib "eagle-import") (part "HEADER/MALE/01"))
    )
    (comp (ref "TNSY_MISO")
      (value "HEADER/MALE/01")
      (footprint "eagle-import:HEADER_MALE_01")
      (fields (field (name "SPICEPREFIX") "X"))
      (libsource (lib "eagle-import") (part "HEADER/MALE/01"))
    )
    (comp (ref "TNSY_MOSI")
      (value "HEADER/MALE/01")
      (footprint "eagle-import:HEADER_MALE_01")
      (fields (field (name "SPICEPREFIX") "X"))
      (libsource (lib "eagle-import") (part "HEADER/MALE/01"))
    )
    (comp (ref "TNSY_SCK")
      (value "HEADER/MALE/01")
      (footprint "eagle-import:HEADER_MALE_01")
      (fields (field (name "SPICEPREFIX") "X"))
      (libsource (lib "eagle-import") (part "HEADER/MALE/01"))
    )
    (comp (ref "TNSY_VIN")
      (value "HEADER/MALE/01")
      (footprint "eagle-import:HEADER_MALE_01")
      (fields (field (name "SPICEPREFIX") "X"))
      (libsource (lib "eagle-import") (part "HEADER/MALE/01"))
    )
  )
  (nets
    (net (code "1") (name "+12V") (class "Default")
      (node (ref "+V") (pin "1") (pinfunction "3_1") (pintype "passive"))
      (node (ref "+V2") (pin "1") (pinfunction "3_1") (pintype "passive"))
      (node (ref "+V3") (pin "1") (pinfunction "3_1") (pintype "passive"))
      (node (ref "12V") (pin "1") (pinfunction "3_1") (pintype "passive"))
      (node (ref "C1") (pin "+") (pinfunction "+_+") (pintype "passive"))
      (node (ref "IC2") (pin "5") (pinfunction "IN_5") (pintype "input"))
      (node (ref "R21") (pin "2") (pinfunction "2_2") (pintype "passive"))
    )
    (net (code "2") (name "-12V") (class "Default")
      (node (ref "-12V") (pin "1") (pinfunction "3_1") (pintype "passive"))
      (node (ref "-V") (pin "1") (pinfunction "3_1") (pintype "passive"))
      (node (ref "-V1") (pin "1") (pinfunction "3_1") (pintype "passive"))
      (node (ref "-V2") (pin "1") (pinfunction "3_1") (pintype "passive"))
      (node (ref "C2") (pin "-") (pinfunction "-_-") (pintype "passive"))
      (node (ref "R22") (pin "2") (pinfunction "2_2") (pintype "passive"))
    )
    (net (code "3") (name "3.3V") (class "Default")
      (node (ref "3.3V") (pin "1") (pinfunction "3_1") (pintype "passive"))
      (node (ref "3.3V1") (pin "1") (pinfunction "3_1") (pintype "passive"))
      (node (ref "IC1") (pin "8") (pinfunction "8_8") (pintype "passive"))
      (node (ref "IC4") (pin "8") (pinfunction "8_8") (pintype "passive"))
      (node (ref "PIXI_3.3V") (pin "1") (pinfunction "3_1") (pintype "passive"))
      (node (ref "R24") (pin "2") (pinfunction "2_2") (pintype "passive"))
      (node (ref "R28") (pin "2") (pinfunction "2_2") (pintype "passive"))
      (node (ref "TNSY_3.3V") (pin "1") (pinfunction "3_1") (pintype "passive"))
    )
    (net (code "4") (name "5V") (class "Default")
      (node (ref "5V") (pin "1") (pinfunction "3_1") (pintype "passive"))
      (node (ref "5V1") (pin "1") (pinfunction "3_1") (pintype "passive"))
      (node (ref "C3") (pin "+") (pinfunction "+_+") (pintype "passive"))
      (node (ref "IC2") (pin "1") (pinfunction "FB_1") (pintype "input"))
      (node (ref "IC3") (pin "14") (pinfunction "VDD_14") (pintype "power_in"))
      (node (ref "L3") (pin "2") (pinfunction "2_2") (pintype "passive"))
      (node (ref "PIXI_5V") (pin "1") (pinfunction "3_1") (pintype "passive"))
      (node (ref "R26") (pin "2") (pinfunction "2_2") (pintype "passive"))
      (node (ref "R30") (pin "2") (pinfunction "2_2") (pintype "passive"))
      (node (ref "TNSY_VIN") (pin "1") (pinfunction "3_1") (pintype "passive"))
    )
    (net (code "5") (name "GND") (class "Default")
      (node (ref "C1") (pin "-") (pinfunction "-_-") (pintype "passive"))
      (node (ref "C2") (pin "+") (pinfunction "+_+") (pintype "passive"))
      (node (ref "C3") (pin "-") (pinfunction "-_-") (pintype "passive"))
      (node (ref "D1") (pin "A") (pinfunction "A_A") (pintype "passive"))
      (node (ref "D2") (pin "C") (pinfunction "C_C") (pintype "passive"))
      (node (ref "D3") (pin "A") (pinfunction "A_A") (pintype "passive"))
      (node (ref "GND") (pin "1") (pinfunction "3_1") (pintype "passive"))
      (node (ref "GND1") (pin "1") (pinfunction "3_1") (pintype "passive"))
      (node (ref "GND2") (pin "1") (pinfunction "3_1") (pintype "passive"))
      (node (ref "GND3") (pin "1") (pinfunction "3_1") (pintype "passive"))
      (node (ref "IC1") (pin "7") (pinfunction "7_7") (pintype "passive"))
      (node (ref "IC2") (pin "2") (pinfunction "GNDSIG_2") (pintype "input"))
      (node (ref "IC2") (pin "3") (pinfunction "~{ON/OFF}_3") (pintype "input"))
      (node (ref "IC2") (pin "4") (pinfunction "GND_4") (pintype "power_in"))
      (node (ref "IC3") (pin "7") (pinfunction "VSS_7") (pintype "power_in"))
      (node (ref "IC4") (pin "7") (pinfunction "7_7") (pintype "passive"))
      (node (ref "PIXI_GND") (pin "1") (pinfunction "3_1") (pintype "passive"))
      (node (ref "PIXI_GND2") (pin "1") (pinfunction "3_1") (pintype "passive"))
      (node (ref "TNSY_GND") (pin "1") (pinfunction "3_1") (pintype "passive"))
    )
    (net (code "6") (name "Net-(2-3)") (class "Default")
      (node (ref "2") (pin "1") (pinfunction "3_1") (pintype "passive"))
      (node (ref "TNSY_2") (pin "1") (pinfunction "3_1") (pintype "passive"))
    )
    (net (code "7") (name "Net-(3-3)") (class "Default")
      (node (ref "3") (pin "1") (pinfunction "3_1") (pintype "passive"))
      (node (ref "TNSY_3") (pin "1") (pinfunction "3_1") (pintype "passive"))
    )
    (net (code "8") (name "Net-(4-3)") (class "Default")
      (node (ref "4") (pin "1") (pinfunction "3_1") (pintype "passive"))
      (node (ref "TNSY_4") (pin "1") (pinfunction "3_1") (pintype "passive"))
    )
    (net (code "9") (name "Net-(5-3)") (class "Default")
      (node (ref "5") (pin "1") (pinfunction "3_1") (pintype "passive"))
      (node (ref "TNSY_5") (pin "1") (pinfunction "3_1") (pintype "passive"))
    )
    (net (code "10") (name "Net-(6-3)") (class "Default")
      (node (ref "6") (pin "1") (pinfunction "3_1") (pintype "passive"))
      (node (ref "TNSY_6") (pin "1") (pinfunction "3_1") (pintype "passive"))
    )
    (net (code "11") (name "Net-(9_CNV-3)") (class "Default")
      (node (ref "9_CNV") (pin "1") (pinfunction "3_1") (pintype "passive"))
      (node (ref "PIXI_CNV") (pin "1") (pinfunction "3_1") (pintype "passive"))
      (node (ref "TNSY_9") (pin "1") (pinfunction "3_1") (pintype "passive"))
    )
    (net (code "12") (name "Net-(11_MOSI-3)") (class "Default")
      (node (ref "11_MOSI") (pin "1") (pinfunction "3_1") (pintype "passive"))
      (node (ref "PIXI_SDI") (pin "1") (pinfunction "3_1") (pintype "passive"))
      (node (ref "TNSY_MOSI") (pin "1") (pinfunction "3_1") (pintype "passive"))
    )
    (net (code "13") (name "Net-(12_MISO-3)") (class "Default")
      (node (ref "12_MISO") (pin "1") (pinfunction "3_1") (pintype "passive"))
      (node (ref "PIXI_SDO") (pin "1") (pinfunction "3_1") (pintype "passive"))
      (node (ref "TNSY_MISO") (pin "1") (pinfunction "3_1") (pintype "passive"))
    )
    (net (code "14") (name "Net-(12_SCK-3)") (class "Default")
      (node (ref "12_SCK") (pin "1") (pinfunction "3_1") (pintype "passive"))
      (node (ref "PIXI_SCK") (pin "1") (pinfunction "3_1") (pintype "passive"))
      (node (ref "TNSY_SCK") (pin "1") (pinfunction "3_1") (pintype "passive"))
    )
    (net (code "15") (name "Net-(14-3)") (class "Default")
      (node (ref "14") (pin "1") (pinfunction "3_1") (pintype "passive"))
      (node (ref "TNSY_14") (pin "1") (pinfunction "3_1") (pintype "passive"))
    )
    (net (code "16") (name "Net-(15-3)") (class "Default")
      (node (ref "15") (pin "1") (pinfunction "3_1") (pintype "passive"))
      (node (ref "TNSY_15") (pin "1") (pinfunction "3_1") (pintype "passive"))
    )
    (net (code "17") (name "Net-(16-3)") (class "Default")
      (node (ref "16") (pin "1") (pinfunction "3_1") (pintype "passive"))
      (node (ref "TNSY_16") (pin "1") (pinfunction "3_1") (pintype "passive"))
    )
    (net (code "18") (name "Net-(17-3)") (class "Default")
      (node (ref "17") (pin "1") (pinfunction "3_1") (pintype "passive"))
      (node (ref "TNSY_17") (pin "1") (pinfunction "3_1") (pintype "passive"))
    )
    (net (code "19") (name "Net-(18-3)") (class "Default")
      (node (ref "18") (pin "1") (pinfunction "3_1") (pintype "passive"))
      (node (ref "TNSY_18") (pin "1") (pinfunction "3_1") (pintype "passive"))
    )
    (net (code "20") (name "Net-(19-3)") (class "Default")
      (node (ref "19") (pin "1") (pinfunction "3_1") (pintype "passive"))
      (node (ref "TNSY_19") (pin "1") (pinfunction "3_1") (pintype "passive"))
    )
    (net (code "21") (name "Net-(20-3)") (class "Default")
      (node (ref "20") (pin "1") (pinfunction "3_1") (pintype "passive"))
      (node (ref "TNSY_20") (pin "1") (pinfunction "3_1") (pintype "passive"))
    )
    (net (code "22") (name "Net-(21-3)") (class "Default")
      (node (ref "21") (pin "1") (pinfunction "3_1") (pintype "passive"))
      (node (ref "TNSY_21") (pin "1") (pinfunction "3_1") (pintype "passive"))
    )
    (net (code "23") (name "Net-(22-3)") (class "Default")
      (node (ref "22") (pin "1") (pinfunction "3_1") (pintype "passive"))
      (node (ref "TNSY_22") (pin "1") (pinfunction "3_1") (pintype "passive"))
    )
    (net (code "24") (name "Net-(23-3)") (class "Default")
      (node (ref "23") (pin "1") (pinfunction "3_1") (pintype "passive"))
      (node (ref "TNSY_23") (pin "1") (pinfunction "3_1") (pintype "passive"))
    )
    (net (code "25") (name "Net-(AVDDIO-3)") (class "Default")
      (node (ref "AVDDIO") (pin "1") (pinfunction "3_1") (pintype "passive"))
      (node (ref "AVDDIO1") (pin "1") (pinfunction "3_1") (pintype "passive"))
      (node (ref "D3") (pin "C") (pinfunction "C_C") (pintype "passive"))
      (node (ref "R21") (pin "1") (pinfunction "1_1") (pintype "passive"))
    )
    (net (code "26") (name "Net-(AVSSIO-3)") (class "Default")
      (node (ref "AVSSIO") (pin "1") (pinfunction "3_1") (pintype "passive"))
      (node (ref "AVSSIO1") (pin "1") (pinfunction "3_1") (pintype "passive"))
      (node (ref "D2") (pin "A") (pinfunction "A_A") (pintype "passive"))
      (node (ref "R22") (pin "1") (pinfunction "1_1") (pintype "passive"))
    )
    (net (code "27") (name "Net-(D4-PadC)") (class "Default")
      (node (ref "D4") (pin "C") (pinfunction "C_C") (pintype "passive"))
      (node (ref "IC1") (pin "1") (pinfunction "1_1") (pintype "passive"))
      (node (ref "R23") (pin "2") (pinfunction "2_2") (pintype "passive"))
    )
    (net (code "28") (name "Net-(D5-PadC)") (class "Default")
      (node (ref "D5") (pin "C") (pinfunction "C_C") (pintype "passive"))
      (node (ref "IC4") (pin "1") (pinfunction "1_1") (pintype "passive"))
      (node (ref "R27") (pin "2") (pinfunction "2_2") (pintype "passive"))
    )
    (net (code "29") (name "Net-(IC2-OUT)") (class "Default")
      (node (ref "D1") (pin "C") (pinfunction "C_C") (pintype "passive"))
      (node (ref "IC2") (pin "7") (pinfunction "OUT_7") (pintype "passive"))
      (node (ref "L3") (pin "1") (pinfunction "1_1") (pintype "passive"))
    )
    (net (code "30") (name "Net-(IC3A-O)") (class "Default")
      (node (ref "IC3") (pin "2") (pinfunction "O_2") (pintype "output"))
      (node (ref "IC3") (pin "3") (pinfunction "I_3") (pintype "input"))
    )
    (net (code "31") (name "Net-(IC3B-O)") (class "Default")
      (node (ref "IC3") (pin "4") (pinfunction "O_4") (pintype "output"))
      (node (ref "R25") (pin "2") (pinfunction "2_2") (pintype "passive"))
    )
    (net (code "32") (name "Net-(IC3E-O)") (class "Default")
      (node (ref "IC3") (pin "10") (pinfunction "O_10") (pintype "output"))
      (node (ref "IC3") (pin "13") (pinfunction "I_13") (pintype "input"))
    )
    (net (code "33") (name "Net-(IC3F-O)") (class "Default")
      (node (ref "IC3") (pin "12") (pinfunction "O_12") (pintype "output"))
      (node (ref "R29") (pin "2") (pinfunction "2_2") (pintype "passive"))
    )
    (net (code "34") (name "Net-(IO_0-3)") (class "Default")
      (node (ref "IO_0") (pin "1") (pinfunction "3_1") (pintype "passive"))
      (node (ref "R1") (pin "2") (pinfunction "2_2") (pintype "passive"))
    )
    (net (code "35") (name "Net-(IO_1-3)") (class "Default")
      (node (ref "IO_1") (pin "1") (pinfunction "3_1") (pintype "passive"))
      (node (ref "R2") (pin "2") (pinfunction "2_2") (pintype "passive"))
    )
    (net (code "36") (name "Net-(IO_2-3)") (class "Default")
      (node (ref "IO_2") (pin "1") (pinfunction "3_1") (pintype "passive"))
      (node (ref "R3") (pin "2") (pinfunction "2_2") (pintype "passive"))
    )
    (net (code "37") (name "Net-(IO_3-3)") (class "Default")
      (node (ref "IO_3") (pin "1") (pinfunction "3_1") (pintype "passive"))
      (node (ref "R4") (pin "2") (pinfunction "2_2") (pintype "passive"))
    )
    (net (code "38") (name "Net-(IO_4-3)") (class "Default")
      (node (ref "IO_4") (pin "1") (pinfunction "3_1") (pintype "passive"))
      (node (ref "R5") (pin "2") (pinfunction "2_2") (pintype "passive"))
    )
    (net (code "39") (name "Net-(IO_5-3)") (class "Default")
      (node (ref "IO_5") (pin "1") (pinfunction "3_1") (pintype "passive"))
      (node (ref "R6") (pin "2") (pinfunction "2_2") (pintype "passive"))
    )
    (net (code "40") (name "Net-(IO_6-3)") (class "Default")
      (node (ref "IO_6") (pin "1") (pinfunction "3_1") (pintype "passive"))
      (node (ref "R7") (pin "2") (pinfunction "2_2") (pintype "passive"))
    )
    (net (code "41") (name "Net-(IO_7-3)") (class "Default")
      (node (ref "IO_7") (pin "1") (pinfunction "3_1") (pintype "passive"))
      (node (ref "R8") (pin "2") (pinfunction "2_2") (pintype "passive"))
    )
    (net (code "42") (name "Net-(IO_8-3)") (class "Default")
      (node (ref "IO_8") (pin "1") (pinfunction "3_1") (pintype "passive"))
      (node (ref "R9") (pin "2") (pinfunction "2_2") (pintype "passive"))
    )
    (net (code "43") (name "Net-(IO_9-3)") (class "Default")
      (node (ref "IO_9") (pin "1") (pinfunction "3_1") (pintype "passive"))
      (node (ref "R10") (pin "2") (pinfunction "2_2") (pintype "passive"))
    )
    (net (code "44") (name "Net-(IO_10-3)") (class "Default")
      (node (ref "IO_10") (pin "1") (pinfunction "3_1") (pintype "passive"))
      (node (ref "R11") (pin "2") (pinfunction "2_2") (pintype "passive"))
    )
    (net (code "45") (name "Net-(IO_11-3)") (class "Default")
      (node (ref "IO_11") (pin "1") (pinfunction "3_1") (pintype "passive"))
      (node (ref "R12") (pin "2") (pinfunction "2_2") (pintype "passive"))
    )
    (net (code "46") (name "Net-(IO_12-3)") (class "Default")
      (node (ref "IO_12") (pin "1") (pinfunction "3_1") (pintype "passive"))
      (node (ref "R13") (pin "2") (pinfunction "2_2") (pintype "passive"))
    )
    (net (code "47") (name "Net-(IO_13-3)") (class "Default")
      (node (ref "IO_13") (pin "1") (pinfunction "3_1") (pintype "passive"))
      (node (ref "R14") (pin "2") (pinfunction "2_2") (pintype "passive"))
    )
    (net (code "48") (name "Net-(IO_14-3)") (class "Default")
      (node (ref "IO_14") (pin "1") (pinfunction "3_1") (pintype "passive"))
      (node (ref "R15") (pin "2") (pinfunction "2_2") (pintype "passive"))
    )
    (net (code "49") (name "Net-(IO_15-3)") (class "Default")
      (node (ref "IO_15") (pin "1") (pinfunction "3_1") (pintype "passive"))
      (node (ref "R16") (pin "2") (pinfunction "2_2") (pintype "passive"))
    )
    (net (code "50") (name "Net-(IO_16-3)") (class "Default")
      (node (ref "IO_16") (pin "1") (pinfunction "3_1") (pintype "passive"))
      (node (ref "R17") (pin "2") (pinfunction "2_2") (pintype "passive"))
    )
    (net (code "51") (name "Net-(IO_17-3)") (class "Default")
      (node (ref "IO_17") (pin "1") (pinfunction "3_1") (pintype "passive"))
      (node (ref "R18") (pin "2") (pinfunction "2_2") (pintype "passive"))
    )
    (net (code "52") (name "Net-(IO_18-3)") (class "Default")
      (node (ref "IO_18") (pin "1") (pinfunction "3_1") (pintype "passive"))
      (node (ref "R19") (pin "2") (pinfunction "2_2") (pintype "passive"))
    )
    (net (code "53") (name "Net-(IO_19-3)") (class "Default")
      (node (ref "IO_19") (pin "1") (pinfunction "3_1") (pintype "passive"))
      (node (ref "R20") (pin "2") (pinfunction "2_2") (pintype "passive"))
    )
    (net (code "54") (name "Net-(MIDI_IN4-3)") (class "Default")
      (node (ref "MIDI_IN4") (pin "1") (pinfunction "3_1") (pintype "passive"))
      (node (ref "R23") (pin "1") (pinfunction "1_1") (pintype "passive"))
    )
    (net (code "55") (name "Net-(MIDI_IN4_2-3)") (class "Default")
      (node (ref "MIDI_IN4_2") (pin "1") (pinfunction "3_1") (pintype "passive"))
      (node (ref "R27") (pin "1") (pinfunction "1_1") (pintype "passive"))
    )
    (net (code "56") (name "Net-(MIDI_IN5-3)") (class "Default")
      (node (ref "D4") (pin "A") (pinfunction "A_A") (pintype "passive"))
      (node (ref "IC1") (pin "2") (pinfunction "2_2") (pintype "passive"))
      (node (ref "MIDI_IN5") (pin "1") (pinfunction "3_1") (pintype "passive"))
    )
    (net (code "57") (name "Net-(MIDI_IN5_2-3)") (class "Default")
      (node (ref "D5") (pin "A") (pinfunction "A_A") (pintype "passive"))
      (node (ref "IC4") (pin "2") (pinfunction "2_2") (pintype "passive"))
      (node (ref "MIDI_IN5_2") (pin "1") (pinfunction "3_1") (pintype "passive"))
    )
    (net (code "58") (name "Net-(MIDI_OUT4-3)") (class "Default")
      (node (ref "MIDI_OUT4") (pin "1") (pinfunction "3_1") (pintype "passive"))
      (node (ref "R26") (pin "1") (pinfunction "1_1") (pintype "passive"))
    )
    (net (code "59") (name "Net-(MIDI_OUT4_2-3)") (class "Default")
      (node (ref "MIDI_OUT4_2") (pin "1") (pinfunction "3_1") (pintype "passive"))
      (node (ref "R30") (pin "1") (pinfunction "1_1") (pintype "passive"))
    )
    (net (code "60") (name "Net-(MIDI_OUT5-3)") (class "Default")
      (node (ref "MIDI_OUT5") (pin "1") (pinfunction "3_1") (pintype "passive"))
      (node (ref "R25") (pin "1") (pinfunction "1_1") (pintype "passive"))
    )
    (net (code "61") (name "Net-(MIDI_OUT5_2-3)") (class "Default")
      (node (ref "MIDI_OUT5_2") (pin "1") (pinfunction "3_1") (pintype "passive"))
      (node (ref "R29") (pin "1") (pinfunction "1_1") (pintype "passive"))
    )
    (net (code "62") (name "Net-(PIXI_0-3)") (class "Default")
      (node (ref "PIXI_0") (pin "1") (pinfunction "3_1") (pintype "passive"))
      (node (ref "R1") (pin "1") (pinfunction "1_1") (pintype "passive"))
    )
    (net (code "63") (name "Net-(PIXI_1-3)") (class "Default")
      (node (ref "PIXI_1") (pin "1") (pinfunction "3_1") (pintype "passive"))
      (node (ref "R2") (pin "1") (pinfunction "1_1") (pintype "passive"))
    )
    (net (code "64") (name "Net-(PIXI_2-3)") (class "Default")
      (node (ref "PIXI_2") (pin "1") (pinfunction "3_1") (pintype "passive"))
      (node (ref "R3") (pin "1") (pinfunction "1_1") (pintype "passive"))
    )
    (net (code "65") (name "Net-(PIXI_3-3)") (class "Default")
      (node (ref "PIXI_3") (pin "1") (pinfunction "3_1") (pintype "passive"))
      (node (ref "R4") (pin "1") (pinfunction "1_1") (pintype "passive"))
    )
    (net (code "66") (name "Net-(PIXI_4-3)") (class "Default")
      (node (ref "PIXI_4") (pin "1") (pinfunction "3_1") (pintype "passive"))
      (node (ref "R5") (pin "1") (pinfunction "1_1") (pintype "passive"))
    )
    (net (code "67") (name "Net-(PIXI_5-3)") (class "Default")
      (node (ref "PIXI_5") (pin "1") (pinfunction "3_1") (pintype "passive"))
      (node (ref "R6") (pin "1") (pinfunction "1_1") (pintype "passive"))
    )
    (net (code "68") (name "Net-(PIXI_6-3)") (class "Default")
      (node (ref "PIXI_6") (pin "1") (pinfunction "3_1") (pintype "passive"))
      (node (ref "R7") (pin "1") (pinfunction "1_1") (pintype "passive"))
    )
    (net (code "69") (name "Net-(PIXI_7-3)") (class "Default")
      (node (ref "PIXI_7") (pin "1") (pinfunction "3_1") (pintype "passive"))
      (node (ref "R8") (pin "1") (pinfunction "1_1") (pintype "passive"))
    )
    (net (code "70") (name "Net-(PIXI_8-3)") (class "Default")
      (node (ref "PIXI_8") (pin "1") (pinfunction "3_1") (pintype "passive"))
      (node (ref "R9") (pin "1") (pinfunction "1_1") (pintype "passive"))
    )
    (net (code "71") (name "Net-(PIXI_9-3)") (class "Default")
      (node (ref "PIXI_9") (pin "1") (pinfunction "3_1") (pintype "passive"))
      (node (ref "R10") (pin "1") (pinfunction "1_1") (pintype "passive"))
    )
    (net (code "72") (name "Net-(PIXI_10-3)") (class "Default")
      (node (ref "PIXI_10") (pin "1") (pinfunction "3_1") (pintype "passive"))
      (node (ref "R11") (pin "1") (pinfunction "1_1") (pintype "passive"))
    )
    (net (code "73") (name "Net-(PIXI_11-3)") (class "Default")
      (node (ref "PIXI_11") (pin "1") (pinfunction "3_1") (pintype "passive"))
      (node (ref "R12") (pin "1") (pinfunction "1_1") (pintype "passive"))
    )
    (net (code "74") (name "Net-(PIXI_12-3)") (class "Default")
      (node (ref "PIXI_12") (pin "1") (pinfunction "3_1") (pintype "passive"))
      (node (ref "R13") (pin "1") (pinfunction "1_1") (pintype "passive"))
    )
    (net (code "75") (name "Net-(PIXI_13-3)") (class "Default")
      (node (ref "PIXI_13") (pin "1") (pinfunction "3_1") (pintype "passive"))
      (node (ref "R14") (pin "1") (pinfunction "1_1") (pintype "passive"))
    )
    (net (code "76") (name "Net-(PIXI_14-3)") (class "Default")
      (node (ref "PIXI_14") (pin "1") (pinfunction "3_1") (pintype "passive"))
      (node (ref "R15") (pin "1") (pinfunction "1_1") (pintype "passive"))
    )
    (net (code "77") (name "Net-(PIXI_15-3)") (class "Default")
      (node (ref "PIXI_15") (pin "1") (pinfunction "3_1") (pintype "passive"))
      (node (ref "R16") (pin "1") (pinfunction "1_1") (pintype "passive"))
    )
    (net (code "78") (name "Net-(PIXI_16-3)") (class "Default")
      (node (ref "PIXI_16") (pin "1") (pinfunction "3_1") (pintype "passive"))
      (node (ref "R17") (pin "1") (pinfunction "1_1") (pintype "passive"))
    )
    (net (code "79") (name "Net-(PIXI_17-3)") (class "Default")
      (node (ref "PIXI_17") (pin "1") (pinfunction "3_1") (pintype "passive"))
      (node (ref "R18") (pin "1") (pinfunction "1_1") (pintype "passive"))
    )
    (net (code "80") (name "Net-(PIXI_18-3)") (class "Default")
      (node (ref "PIXI_18") (pin "1") (pinfunction "3_1") (pintype "passive"))
      (node (ref "R19") (pin "1") (pinfunction "1_1") (pintype "passive"))
    )
    (net (code "81") (name "Net-(PIXI_19-3)") (class "Default")
      (node (ref "PIXI_19") (pin "1") (pinfunction "3_1") (pintype "passive"))
      (node (ref "R20") (pin "1") (pinfunction "1_1") (pintype "passive"))
    )
    (net (code "82") (name "Net-(PIXI_CS-3)") (class "Default")
      (node (ref "PIXI_CS") (pin "1") (pinfunction "3_1") (pintype "passive"))
      (node (ref "TNSY_CS") (pin "1") (pinfunction "3_1") (pintype "passive"))
    )
    (net (code "83") (name "RX1") (class "Default")
      (node (ref "IC1") (pin "6") (pinfunction "6_6") (pintype "passive"))
      (node (ref "R24") (pin "1") (pinfunction "1_1") (pintype "passive"))
      (node (ref "TNSY_0") (pin "1") (pinfunction "3_1") (pintype "passive"))
    )
    (net (code "84") (name "RX2") (class "Default")
      (node (ref "IC4") (pin "6") (pinfunction "6_6") (pintype "passive"))
      (node (ref "R28") (pin "1") (pinfunction "1_1") (pintype "passive"))
      (node (ref "TNSY_7") (pin "1") (pinfunction "3_1") (pintype "passive"))
    )
    (net (code "85") (name "TX1") (class "Default")
      (node (ref "IC3") (pin "1") (pinfunction "I_1") (pintype "input"))
      (node (ref "TNSY_1") (pin "1") (pinfunction "3_1") (pintype "passive"))
    )
    (net (code "86") (name "TX2") (class "Default")
      (node (ref "IC3") (pin "11") (pinfunction "I_11") (pintype "input"))
      (node (ref "TNSY_8") (pin "1") (pinfunction "3_1") (pintype "passive"))
    )
    (net (code "87") (name "unconnected-(IC1-Pad3)") (class "Default")
      (node (ref "IC1") (pin "3") (pinfunction "3_3") (pintype "passive"))
    )
    (net (code "88") (name "unconnected-(IC1-Pad4)") (class "Default")
      (node (ref "IC1") (pin "4") (pinfunction "4_4") (pintype "passive"))
    )
    (net (code "89") (name "unconnected-(IC1-Pad5)") (class "Default")
      (node (ref "IC1") (pin "5") (pinfunction "5_5") (pintype "passive"))
    )
    (net (code "90") (name "unconnected-(IC4-Pad3)") (class "Default")
      (node (ref "IC4") (pin "3") (pinfunction "3_3") (pintype "passive"))
    )
    (net (code "91") (name "unconnected-(IC4-Pad4)") (class "Default")
      (node (ref "IC4") (pin "4") (pinfunction "4_4") (pintype "passive"))
    )
    (net (code "92") (name "unconnected-(IC4-Pad5)") (class "Default")
      (node (ref "IC4") (pin "5") (pinfunction "5_5") (pintype "passive"))
    )
    (net (code "93") (name "unconnected-(PIXI_INT-3-Pad1)") (class "Default")
      (node (ref "PIXI_INT") (pin "1") (pinfunction "3_1") (pintype "passive"))
    )
    (net (code "94") (name "unconnected-(PIXI_NC1-3-Pad1)") (class "Default")
      (node (ref "PIXI_NC1") (pin "1") (pinfunction "3_1") (pintype "passive"))
    )
    (net (code "95") (name "unconnected-(PIXI_NC2-3-Pad1)") (class "Default")
      (node (ref "PIXI_NC2") (pin "1") (pinfunction "3_1") (pintype "passive"))
    )
    (net (code "96") (name "unconnected-(PIXI_NC3-3-Pad1)") (class "Default")
      (node (ref "PIXI_NC3") (pin "1") (pinfunction "3_1") (pintype "passive"))
    )
    (net (code "97") (name "unconnected-(PIXI_NC4-3-Pad1)") (class "Default")
      (node (ref "PIXI_NC4") (pin "1") (pinfunction "3_1") (pintype "passive"))
    )
    (net (code "98") (name "unconnected-(PIXI_NC5-3-Pad1)") (class "Default")
      (node (ref "PIXI_NC5") (pin "1") (pinfunction "3_1") (pintype "passive"))
    )
    (net (code "99") (name "unconnected-(PIXI_NC6-3-Pad1)") (class "Default")
      (node (ref "PIXI_NC6") (pin "1") (pinfunction "3_1") (pintype "passive"))
    )
    (net (code "100") (name "unconnected-(TNSY_GND2-3-Pad1)") (class "Default")
      (node (ref "TNSY_GND2") (pin "1") (pinfunction "3_1") (pintype "passive"))
    )
  )
)
